# vaSmd-V3.net
KiCad netlist of a schematic drawn in Altium Designer
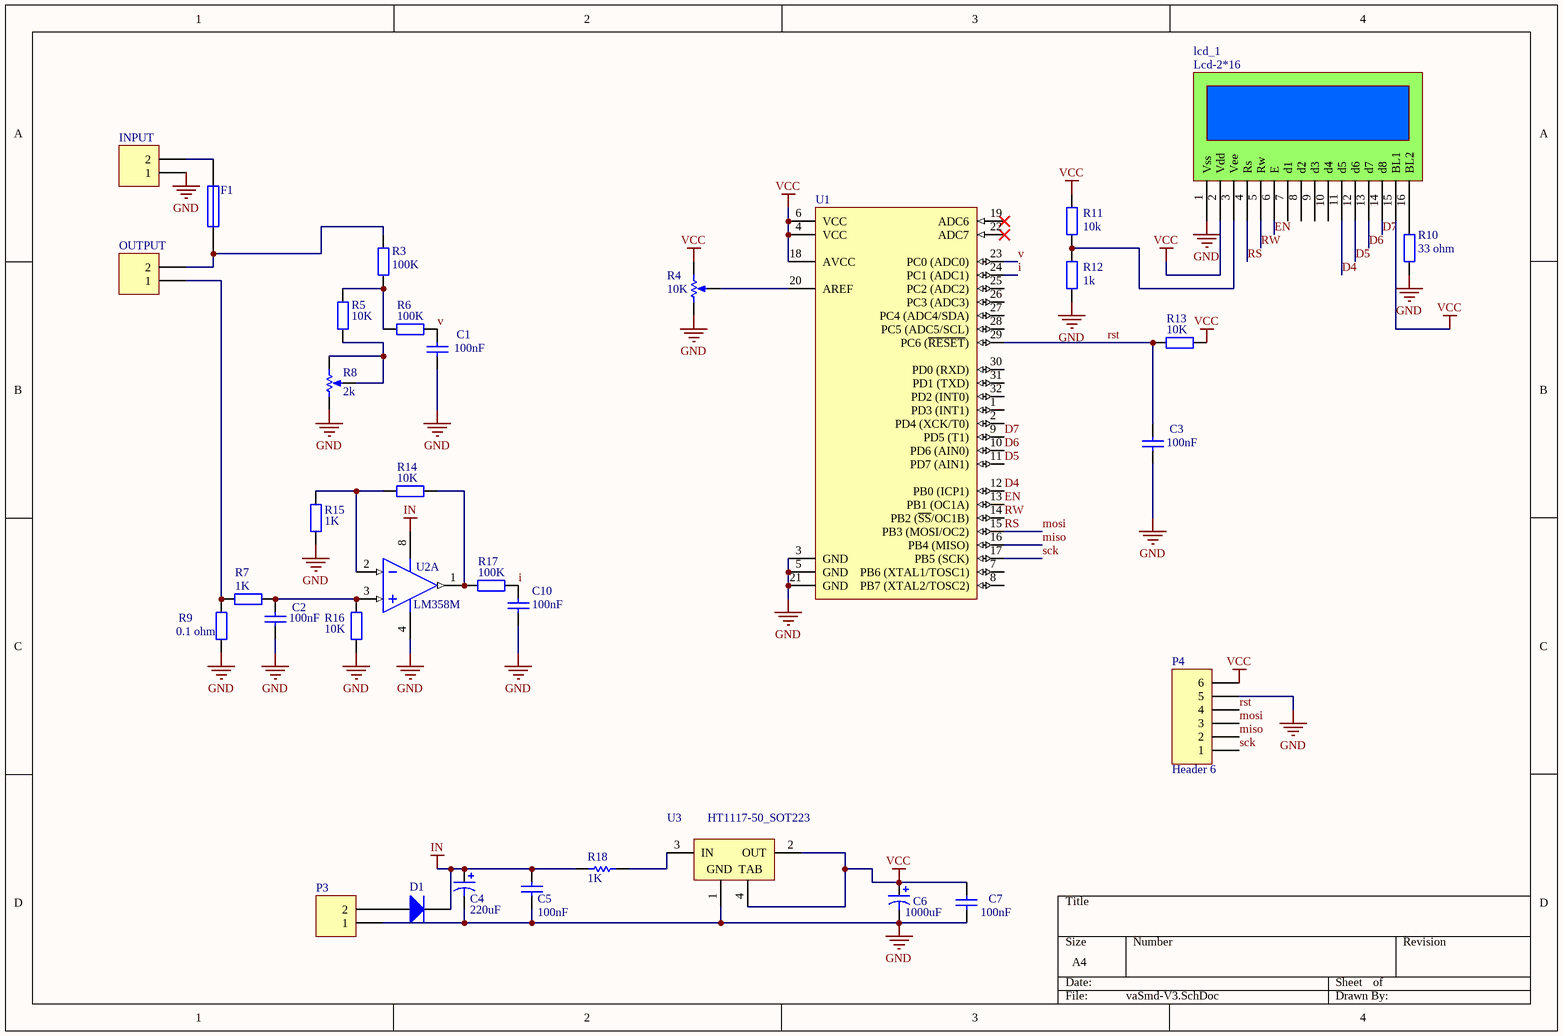
[diagram p0: vaSmd-V3.SchDoc]

(export (version "E")
  (design (tool "Eeschema 10.0.6"))
  (components
    (comp (ref "C1")
      (value "100nF")
      (footprint "RESC3216m")
      (description "Capacitor")
      (fields (field (name "PUBLISHER") "Altium Limited"))
      (libsource (lib "Miscellaneous Devices") (part "Cap"))
    )
    (comp (ref "C2")
      (value "100nF")
      (footprint "RESC3216m")
      (description "Capacitor")
      (fields (field (name "PUBLISHER") "Altium Limited"))
      (libsource (lib "Miscellaneous Devices") (part "Cap"))
    )
    (comp (ref "C3")
      (value "100nF")
      (footprint "RESC3216m")
      (description "Capacitor")
      (fields (field (name "PUBLISHER") "Altium Limited"))
      (libsource (lib "Miscellaneous Devices") (part "Cap"))
    )
    (comp (ref "C4")
      (value "220uF")
      (footprint "cap_smd_10*10.5")
      (description "Polarized Capacitor (Radial)")
      (fields (field (name "PUBLISHER") "Altium Limited"))
      (libsource (lib "Miscellaneous Devices") (part "Cap Pol1"))
    )
    (comp (ref "C5")
      (value "100nF")
      (footprint "RESC3216m")
      (description "Capacitor")
      (fields (field (name "PUBLISHER") "Altium Limited"))
      (libsource (lib "Miscellaneous Devices") (part "Cap"))
    )
    (comp (ref "C6")
      (value "1000uF")
      (footprint "cap_smd_10*10.5")
      (description "Polarized Capacitor (Radial)")
      (fields (field (name "PUBLISHER") "Altium Limited"))
      (libsource (lib "Miscellaneous Devices") (part "Cap Pol1"))
    )
    (comp (ref "C7")
      (value "100nF")
      (footprint "RESC3216m")
      (description "Capacitor")
      (fields (field (name "PUBLISHER") "Altium Limited"))
      (libsource (lib "Miscellaneous Devices") (part "Cap"))
    )
    (comp (ref "C10")
      (value "100nF")
      (footprint "RESC3216m")
      (description "Capacitor")
      (fields (field (name "PUBLISHER") "Altium Limited"))
      (libsource (lib "Miscellaneous Devices") (part "Cap"))
    )
    (comp (ref "D1")
      (value "~")
      (footprint "DO-35")
      (description "High Conductance Fast Diode")
      (fields (field (name "PUBLISHER") "Altium Limited"))
      (libsource (lib "Miscellaneous Devices") (part "Diode 1N4148"))
    )
    (comp (ref "F1")
      (value "~")
      (footprint "fuse1")
      (description "Fuse")
      (fields (field (name "PUBLISHER") "Altium Limited"))
      (libsource (lib "Miscellaneous Devices") (part "Fuse 1"))
    )
    (comp (ref "INPUT")
      (value "~")
      (footprint "terminal_2pin")
      (description "Header, 2-Pin")
      (fields (field (name "PUBLISHER") "Altium Limited"))
      (libsource (lib "Miscellaneous Connectors") (part "Header 2"))
    )
    (comp (ref "lcd_1") (value "~") (footprint "HDR1X16") (libsource (lib "Schlib1") (part "lcd-2*16")))
    (comp (ref "OUTPUT")
      (value "~")
      (footprint "terminal_2pin")
      (description "Header, 2-Pin")
      (fields (field (name "PUBLISHER") "Altium Limited"))
      (libsource (lib "Miscellaneous Connectors") (part "Header 2"))
    )
    (comp (ref "P3")
      (value "~")
      (footprint "Mokhaberati_2pin")
      (description "Header, 2-Pin")
      (fields (field (name "PUBLISHER") "Altium Limited"))
      (libsource (lib "Miscellaneous Connectors") (part "Header 2"))
    )
    (comp (ref "P4")
      (value "Header 6")
      (footprint "Mokhaberati_6pin")
      (description "Header, 6-Pin")
      (fields (field (name "PUBLISHER") "Altium Limited"))
      (libsource (lib "Miscellaneous Connectors") (part "Header 6"))
    )
    (comp (ref "R3")
      (value "100K")
      (footprint "RESC3216m")
      (description "Resistor")
      (fields (field (name "PUBLISHER") "Altium Limited"))
      (libsource (lib "") (part "Res2_1"))
    )
    (comp (ref "R4")
      (value "10K")
      (footprint "VR5")
      (description "Potentiometer")
      (fields (field (name "PUBLISHER") "Altium Limited"))
      (libsource (lib "Miscellaneous Devices") (part "RPot"))
    )
    (comp (ref "R5")
      (value "10K")
      (footprint "RESC3216m")
      (description "Resistor")
      (fields (field (name "PUBLISHER") "Altium Limited"))
      (libsource (lib "") (part "Res2_1"))
    )
    (comp (ref "R6")
      (value "100K")
      (footprint "RESC3216m")
      (description "Resistor")
      (fields (field (name "PUBLISHER") "Altium Limited"))
      (libsource (lib "Miscellaneous Devices") (part "Res2"))
    )
    (comp (ref "R7")
      (value "1K")
      (footprint "RESC3216m")
      (description "Resistor")
      (fields (field (name "PUBLISHER") "Altium Limited"))
      (libsource (lib "Miscellaneous Devices") (part "Res2"))
    )
    (comp (ref "R8")
      (value "2k")
      (footprint "VR5")
      (description "Potentiometer")
      (fields (field (name "PUBLISHER") "Altium Limited"))
      (libsource (lib "Miscellaneous Devices") (part "RPot"))
    )
    (comp (ref "R9")
      (value "0.1 ohm")
      (footprint "AXIAL-0.9")
      (description "Resistor")
      (fields (field (name "PUBLISHER") "Altium Limited"))
      (libsource (lib "") (part "Res2_1"))
    )
    (comp (ref "R10")
      (value "33 ohm")
      (footprint "RESC3216m")
      (description "Resistor")
      (fields (field (name "PUBLISHER") "Altium Limited"))
      (libsource (lib "") (part "Res2_1"))
    )
    (comp (ref "R11")
      (value "10k")
      (footprint "RESC3216m")
      (description "Resistor")
      (fields (field (name "PUBLISHER") "Altium Limited"))
      (libsource (lib "") (part "Res2_1"))
    )
    (comp (ref "R12")
      (value "1k")
      (footprint "RESC3216m")
      (description "Resistor")
      (fields (field (name "PUBLISHER") "Altium Limited"))
      (libsource (lib "") (part "Res2_1"))
    )
    (comp (ref "R13")
      (value "10K")
      (footprint "RESC3216m")
      (description "Resistor")
      (fields (field (name "PUBLISHER") "Altium Limited"))
      (libsource (lib "Miscellaneous Devices") (part "Res2"))
    )
    (comp (ref "R14")
      (value "10K")
      (footprint "RESC3216m")
      (description "Resistor")
      (fields (field (name "PUBLISHER") "Altium Limited"))
      (libsource (lib "Miscellaneous Devices") (part "Res2"))
    )
    (comp (ref "R15")
      (value "1K")
      (footprint "RESC3216m")
      (description "Resistor")
      (fields (field (name "PUBLISHER") "Altium Limited"))
      (libsource (lib "") (part "Res2_1"))
    )
    (comp (ref "R16")
      (value "10K")
      (footprint "RESC3216m")
      (description "Resistor")
      (fields (field (name "PUBLISHER") "Altium Limited"))
      (libsource (lib "") (part "Res2_1"))
    )
    (comp (ref "R17")
      (value "100K")
      (footprint "RESC3216m")
      (description "Resistor")
      (fields (field (name "PUBLISHER") "Altium Limited"))
      (libsource (lib "Miscellaneous Devices") (part "Res2"))
    )
    (comp (ref "R18")
      (value "1K")
      (footprint "AXIAL-0.4")
      (description "Resistor")
      (fields (field (name "Comment") "Res1") (field (name "PUBLISHER") "Altium Limited"))
      (libsource (lib "Miscellaneous Devices") (part "Res1"))
    )
    (comp (ref "U1")
      (value "~")
      (footprint "32A_N")
      (fields (field (name "PUBLISHER") "Altium Limited"))
      (libsource (lib "Atmel Microcontroller 8-Bit megaAVR") (part "ATmega8A-AU"))
    )
    (comp (ref "U2")
      (value "LM358M")
      (footprint "M08A_N")
      (description "Low Power Dual Operational Amplifier, 8-pin Narrow SOIC")
      (fields (field (name "MANUFACTURER") "National Semiconductor"))
      (libsource (lib "National Semiconductor Amplifier") (part "LM358M"))
    )
    (comp (ref "U3")
      (value "HT1117-50_SOT223")
      (footprint "SOT223_N")
      (description "5.0V, 1A General Purpose LDO")
      (libsource (lib "Holtek Semiconductor Power Management") (part "HT1117-50_SOT223"))
    )
  )
  (nets
    (net (code "1") (name "/D4") (class "Default")
      (node (ref "U1") (pin "12") (pinfunction "PB0_(ICP1)_12") (pintype "bidirectional"))
      (node (ref "lcd_1") (pin "11") (pinfunction "d5_11") (pintype "passive"))
    )
    (net (code "2") (name "/D5") (class "Default")
      (node (ref "U1") (pin "11") (pinfunction "PD7_(AIN1)_11") (pintype "bidirectional"))
      (node (ref "lcd_1") (pin "12") (pinfunction "d6_12") (pintype "passive"))
    )
    (net (code "3") (name "/D6") (class "Default")
      (node (ref "U1") (pin "10") (pinfunction "PD6_(AIN0)_10") (pintype "bidirectional"))
      (node (ref "lcd_1") (pin "13") (pinfunction "d7_13") (pintype "passive"))
    )
    (net (code "4") (name "/D7") (class "Default")
      (node (ref "U1") (pin "9") (pinfunction "PD5_(T1)_9") (pintype "bidirectional"))
      (node (ref "lcd_1") (pin "14") (pinfunction "d8_14") (pintype "passive"))
    )
    (net (code "5") (name "/EN") (class "Default")
      (node (ref "U1") (pin "13") (pinfunction "PB1_(OC1A)_13") (pintype "bidirectional"))
      (node (ref "lcd_1") (pin "6") (pinfunction "E_6") (pintype "passive"))
    )
    (net (code "6") (name "/RS") (class "Default")
      (node (ref "P4") (pin "3") (pinfunction "3_3") (pintype "passive"))
      (node (ref "U1") (pin "15") (pinfunction "PB3_(MOSI/OC2)_15") (pintype "bidirectional"))
      (node (ref "lcd_1") (pin "4") (pinfunction "Rs_4") (pintype "passive"))
    )
    (net (code "7") (name "/RW") (class "Default")
      (node (ref "U1") (pin "14") (pinfunction "PB2_(~{SS}/OC1B)_14") (pintype "bidirectional"))
      (node (ref "lcd_1") (pin "5") (pinfunction "Rw_5") (pintype "passive"))
    )
    (net (code "8") (name "/i") (class "Default")
      (node (ref "C10") (pin "2") (pinfunction "2_2") (pintype "passive"))
      (node (ref "R17") (pin "2") (pinfunction "2_2") (pintype "passive"))
      (node (ref "U1") (pin "24") (pinfunction "PC1_(ADC1)_24") (pintype "bidirectional"))
    )
    (net (code "9") (name "/miso") (class "Default")
      (node (ref "P4") (pin "2") (pinfunction "2_2") (pintype "passive"))
      (node (ref "U1") (pin "16") (pinfunction "PB4_(MISO)_16") (pintype "bidirectional"))
    )
    (net (code "10") (name "/rst") (class "Default")
      (node (ref "C3") (pin "2") (pinfunction "2_2") (pintype "passive"))
      (node (ref "P4") (pin "4") (pinfunction "4_4") (pintype "passive"))
      (node (ref "R13") (pin "1") (pinfunction "1_1") (pintype "passive"))
      (node (ref "U1") (pin "29") (pinfunction "PC6_(~{RESET})_29") (pintype "bidirectional"))
    )
    (net (code "11") (name "/sck") (class "Default")
      (node (ref "P4") (pin "1") (pinfunction "1_1") (pintype "passive"))
      (node (ref "U1") (pin "17") (pinfunction "PB5_(SCK)_17") (pintype "bidirectional"))
    )
    (net (code "12") (name "/v") (class "Default")
      (node (ref "C1") (pin "2") (pinfunction "2_2") (pintype "passive"))
      (node (ref "R6") (pin "2") (pinfunction "2_2") (pintype "passive"))
      (node (ref "U1") (pin "23") (pinfunction "PC0_(ADC0)_23") (pintype "bidirectional"))
    )
    (net (code "13") (name "GND") (class "Default")
      (node (ref "C1") (pin "1") (pinfunction "1_1") (pintype "passive"))
      (node (ref "C10") (pin "1") (pinfunction "1_1") (pintype "passive"))
      (node (ref "C2") (pin "1") (pinfunction "1_1") (pintype "passive"))
      (node (ref "C3") (pin "1") (pinfunction "1_1") (pintype "passive"))
      (node (ref "C4") (pin "2") (pinfunction "2_2") (pintype "passive"))
      (node (ref "C5") (pin "1") (pinfunction "1_1") (pintype "passive"))
      (node (ref "C6") (pin "2") (pinfunction "2_2") (pintype "passive"))
      (node (ref "C7") (pin "1") (pinfunction "1_1") (pintype "passive"))
      (node (ref "INPUT") (pin "1") (pinfunction "1_1") (pintype "passive"))
      (node (ref "P3") (pin "1") (pinfunction "1_1") (pintype "passive"))
      (node (ref "P4") (pin "5") (pinfunction "5_5") (pintype "passive"))
      (node (ref "R10") (pin "1") (pinfunction "1_1") (pintype "passive"))
      (node (ref "R12") (pin "1") (pinfunction "1_1") (pintype "passive"))
      (node (ref "R15") (pin "1") (pinfunction "1_1") (pintype "passive"))
      (node (ref "R16") (pin "1") (pinfunction "1_1") (pintype "passive"))
      (node (ref "R4") (pin "1") (pinfunction "TOP_1") (pintype "passive"))
      (node (ref "R8") (pin "1") (pinfunction "TOP_1") (pintype "passive"))
      (node (ref "R9") (pin "1") (pinfunction "1_1") (pintype "passive"))
      (node (ref "U1") (pin "21") (pinfunction "GND_21") (pintype "power_in"))
      (node (ref "U1") (pin "3") (pinfunction "GND_3") (pintype "power_in"))
      (node (ref "U1") (pin "5") (pinfunction "GND_5") (pintype "power_in"))
      (node (ref "U2") (pin "4") (pinfunction "GND_4") (pintype "power_in"))
      (node (ref "U3") (pin "1") (pinfunction "GND_1") (pintype "power_in"))
      (node (ref "lcd_1") (pin "1") (pinfunction "Vss_1") (pintype "passive"))
    )
    (net (code "14") (name "IN") (class "Default")
      (node (ref "C4") (pin "1") (pinfunction "1_1") (pintype "passive"))
      (node (ref "C5") (pin "2") (pinfunction "2_2") (pintype "passive"))
      (node (ref "D1") (pin "2") (pinfunction "K_2") (pintype "passive"))
      (node (ref "R18") (pin "2") (pinfunction "2_2") (pintype "passive"))
      (node (ref "U2") (pin "8") (pinfunction "V+_8") (pintype "power_in"))
    )
    (net (code "15") (name "Net-(D1-A)") (class "Default")
      (node (ref "D1") (pin "1") (pinfunction "A_1") (pintype "passive"))
      (node (ref "P3") (pin "2") (pinfunction "2_2") (pintype "passive"))
    )
    (net (code "16") (name "Net-(F1-Pad1)") (class "Default")
      (node (ref "F1") (pin "1") (pinfunction "1_1") (pintype "passive"))
      (node (ref "INPUT") (pin "2") (pinfunction "2_2") (pintype "passive"))
    )
    (net (code "17") (name "Net-(F1-Pad2)") (class "Default")
      (node (ref "F1") (pin "2") (pinfunction "2_2") (pintype "passive"))
      (node (ref "OUTPUT") (pin "2") (pinfunction "2_2") (pintype "passive"))
      (node (ref "R3") (pin "2") (pinfunction "2_2") (pintype "passive"))
    )
    (net (code "18") (name "Net-(OUTPUT-Pad1)") (class "Default")
      (node (ref "OUTPUT") (pin "1") (pinfunction "1_1") (pintype "passive"))
      (node (ref "R7") (pin "1") (pinfunction "1_1") (pintype "passive"))
      (node (ref "R9") (pin "2") (pinfunction "2_2") (pintype "passive"))
    )
    (net (code "19") (name "Net-(R3-Pad1)") (class "Default")
      (node (ref "R3") (pin "1") (pinfunction "1_1") (pintype "passive"))
      (node (ref "R5") (pin "2") (pinfunction "2_2") (pintype "passive"))
      (node (ref "R6") (pin "1") (pinfunction "1_1") (pintype "passive"))
    )
    (net (code "20") (name "Net-(R4-TAP)") (class "Default")
      (node (ref "R4") (pin "3") (pinfunction "TAP_3") (pintype "passive"))
      (node (ref "U1") (pin "20") (pinfunction "AREF_20") (pintype "power_in"))
    )
    (net (code "21") (name "Net-(R8-BOT)") (class "Default")
      (node (ref "R5") (pin "1") (pinfunction "1_1") (pintype "passive"))
      (node (ref "R8") (pin "2") (pinfunction "BOT_2") (pintype "passive"))
      (node (ref "R8") (pin "3") (pinfunction "TAP_3") (pintype "passive"))
    )
    (net (code "22") (name "Net-(U2A-INA+)") (class "Default")
      (node (ref "C2") (pin "2") (pinfunction "2_2") (pintype "passive"))
      (node (ref "R16") (pin "2") (pinfunction "2_2") (pintype "passive"))
      (node (ref "R7") (pin "2") (pinfunction "2_2") (pintype "passive"))
      (node (ref "U2") (pin "3") (pinfunction "INA+_3") (pintype "input"))
    )
    (net (code "23") (name "Net-(U2A-INA-)") (class "Default")
      (node (ref "R14") (pin "1") (pinfunction "1_1") (pintype "passive"))
      (node (ref "R15") (pin "2") (pinfunction "2_2") (pintype "passive"))
      (node (ref "U2") (pin "2") (pinfunction "INA-_2") (pintype "input"))
    )
    (net (code "24") (name "Net-(U2A-OUTA)") (class "Default")
      (node (ref "R14") (pin "2") (pinfunction "2_2") (pintype "passive"))
      (node (ref "R17") (pin "1") (pinfunction "1_1") (pintype "passive"))
      (node (ref "U2") (pin "1") (pinfunction "OUTA_1") (pintype "output"))
    )
    (net (code "25") (name "Net-(U3-IN)") (class "Default")
      (node (ref "R18") (pin "1") (pinfunction "1_1") (pintype "passive"))
      (node (ref "U3") (pin "3") (pinfunction "IN_3") (pintype "power_in"))
    )
    (net (code "26") (name "Net-(lcd_1-BL2)") (class "Default")
      (node (ref "R10") (pin "2") (pinfunction "2_2") (pintype "passive"))
      (node (ref "lcd_1") (pin "16") (pinfunction "BL2_16") (pintype "passive"))
    )
    (net (code "27") (name "Net-(lcd_1-Vee)") (class "Default")
      (node (ref "R11") (pin "1") (pinfunction "1_1") (pintype "passive"))
      (node (ref "R12") (pin "2") (pinfunction "2_2") (pintype "passive"))
      (node (ref "lcd_1") (pin "3") (pinfunction "Vee_3") (pintype "passive"))
    )
    (net (code "28") (name "VCC") (class "Default")
      (node (ref "C6") (pin "1") (pinfunction "1_1") (pintype "passive"))
      (node (ref "C7") (pin "2") (pinfunction "2_2") (pintype "passive"))
      (node (ref "P4") (pin "6") (pinfunction "6_6") (pintype "passive"))
      (node (ref "R11") (pin "2") (pinfunction "2_2") (pintype "passive"))
      (node (ref "R13") (pin "2") (pinfunction "2_2") (pintype "passive"))
      (node (ref "R4") (pin "2") (pinfunction "BOT_2") (pintype "passive"))
      (node (ref "U1") (pin "18") (pinfunction "AVCC_18") (pintype "power_in"))
      (node (ref "U1") (pin "4") (pinfunction "VCC_4") (pintype "power_in"))
      (node (ref "U1") (pin "6") (pinfunction "VCC_6") (pintype "power_in"))
      (node (ref "U3") (pin "2") (pinfunction "OUT_2") (pintype "power_in"))
      (node (ref "U3") (pin "4") (pinfunction "TAB_4") (pintype "power_in"))
      (node (ref "lcd_1") (pin "15") (pinfunction "BL1_15") (pintype "passive"))
      (node (ref "lcd_1") (pin "2") (pinfunction "Vdd_2") (pintype "passive"))
    )
    (net (code "29") (name "unconnected-(U1-ADC6-Pad19)") (class "Default")
      (node (ref "U1") (pin "19") (pinfunction "ADC6_19") (pintype "input+no_connect"))
    )
    (net (code "30") (name "unconnected-(U1-ADC7-Pad22)") (class "Default")
      (node (ref "U1") (pin "22") (pinfunction "ADC7_22") (pintype "input+no_connect"))
    )
    (net (code "31") (name "unconnected-(U1-PB6_(XTAL1{slash}TOSC1)-Pad7)") (class "Default")
      (node (ref "U1") (pin "7") (pinfunction "PB6_(XTAL1/TOSC1)_7") (pintype "bidirectional"))
    )
    (net (code "32") (name "unconnected-(U1-PB7_(XTAL2{slash}TOSC2)-Pad8)") (class "Default")
      (node (ref "U1") (pin "8") (pinfunction "PB7_(XTAL2/TOSC2)_8") (pintype "bidirectional"))
    )
    (net (code "33") (name "unconnected-(U1-PC2_(ADC2)-Pad25)") (class "Default")
      (node (ref "U1") (pin "25") (pinfunction "PC2_(ADC2)_25") (pintype "bidirectional"))
    )
    (net (code "34") (name "unconnected-(U1-PC3_(ADC3)-Pad26)") (class "Default")
      (node (ref "U1") (pin "26") (pinfunction "PC3_(ADC3)_26") (pintype "bidirectional"))
    )
    (net (code "35") (name "unconnected-(U1-PC4_(ADC4{slash}SDA)-Pad27)") (class "Default")
      (node (ref "U1") (pin "27") (pinfunction "PC4_(ADC4/SDA)_27") (pintype "bidirectional"))
    )
    (net (code "36") (name "unconnected-(U1-PC5_(ADC5{slash}SCL)-Pad28)") (class "Default")
      (node (ref "U1") (pin "28") (pinfunction "PC5_(ADC5/SCL)_28") (pintype "bidirectional"))
    )
    (net (code "37") (name "unconnected-(U1-PD0_(RXD)-Pad30)") (class "Default")
      (node (ref "U1") (pin "30") (pinfunction "PD0_(RXD)_30") (pintype "bidirectional"))
    )
    (net (code "38") (name "unconnected-(U1-PD1_(TXD)-Pad31)") (class "Default")
      (node (ref "U1") (pin "31") (pinfunction "PD1_(TXD)_31") (pintype "bidirectional"))
    )
    (net (code "39") (name "unconnected-(U1-PD2_(INT0)-Pad32)") (class "Default")
      (node (ref "U1") (pin "32") (pinfunction "PD2_(INT0)_32") (pintype "bidirectional"))
    )
    (net (code "40") (name "unconnected-(U1-PD3_(INT1)-Pad1)") (class "Default")
      (node (ref "U1") (pin "1") (pinfunction "PD3_(INT1)_1") (pintype "bidirectional"))
    )
    (net (code "41") (name "unconnected-(U1-PD4_(XCK{slash}T0)-Pad2)") (class "Default")
      (node (ref "U1") (pin "2") (pinfunction "PD4_(XCK/T0)_2") (pintype "bidirectional"))
    )
    (net (code "42") (name "unconnected-(lcd_1-d1-Pad7)") (class "Default")
      (node (ref "lcd_1") (pin "7") (pinfunction "d1_7") (pintype "passive"))
    )
    (net (code "43") (name "unconnected-(lcd_1-d2-Pad8)") (class "Default")
      (node (ref "lcd_1") (pin "8") (pinfunction "d2_8") (pintype "passive"))
    )
    (net (code "44") (name "unconnected-(lcd_1-d3-Pad9)") (class "Default")
      (node (ref "lcd_1") (pin "9") (pinfunction "d3_9") (pintype "passive"))
    )
    (net (code "45") (name "unconnected-(lcd_1-d4-Pad10)") (class "Default")
      (node (ref "lcd_1") (pin "10") (pinfunction "d4_10") (pintype "passive"))
    )
  )
)
